# Power_Sources.net
KiCad netlist of a schematic drawn in Altium Designer
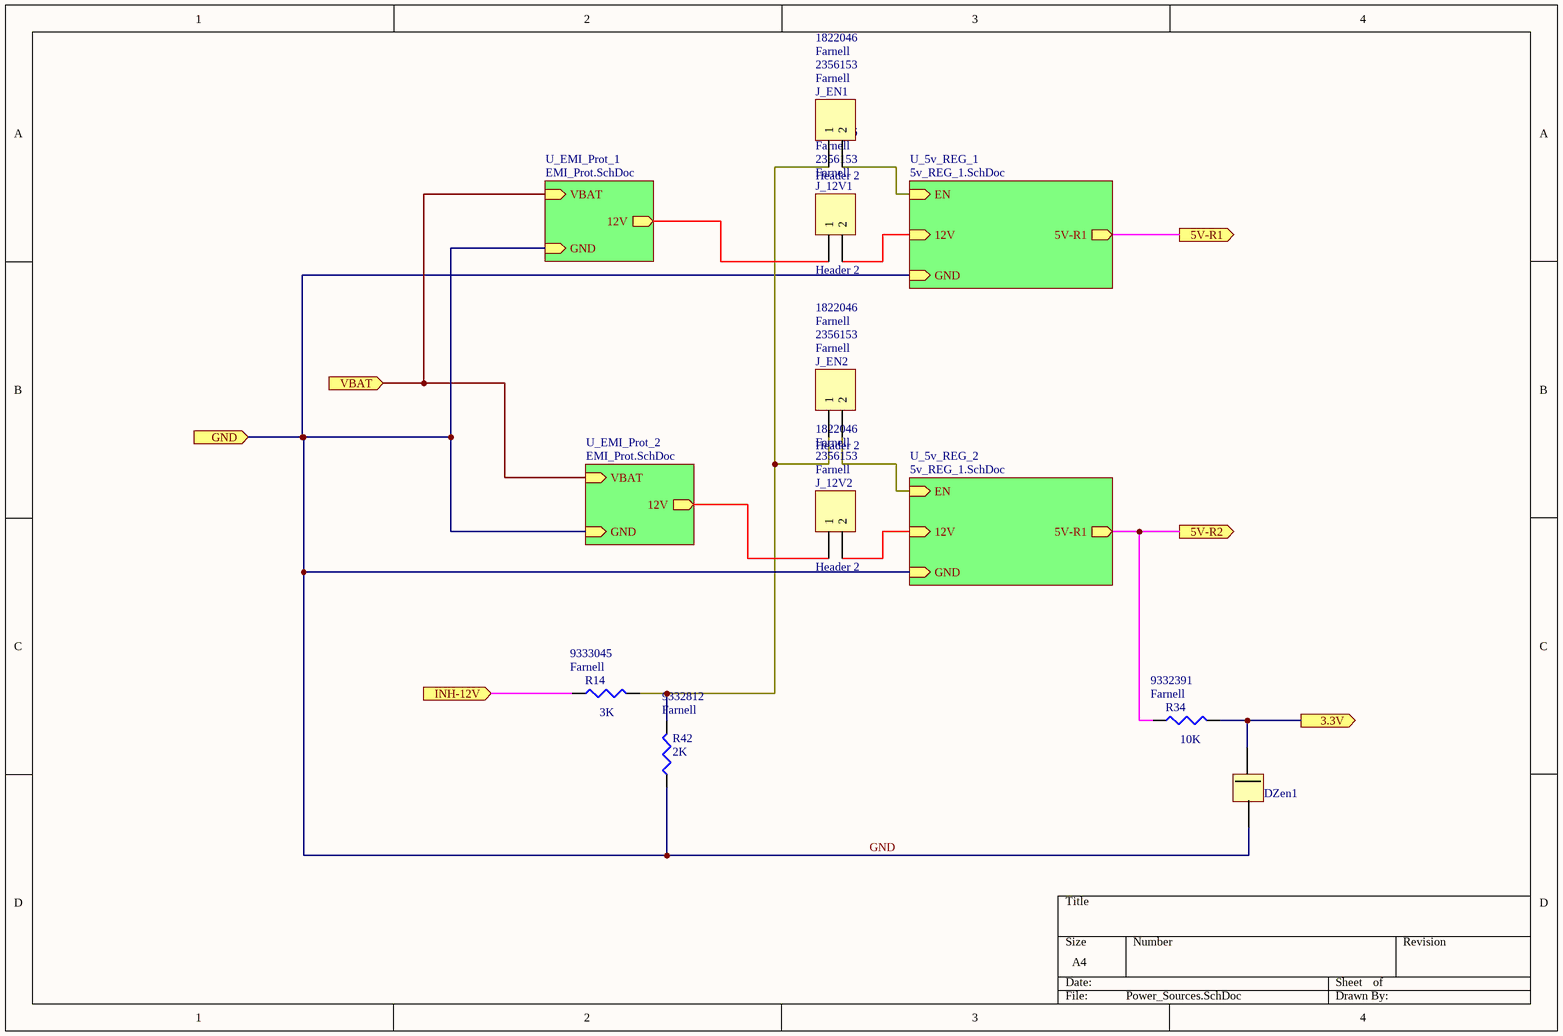
[diagram p0: Power_Sources.SchDoc]

(export (version "E")
  (design (tool "Eeschema 10.0.6"))
  (components
    (comp (ref "DZen1")
      (value "3.3V")
      (footprint "Zener_Diode")
      (description "Zener Diode 3.3V")
      (libsource (lib "Schlib1_HMI3D") (part "D_Zener"))
    )
    (comp (ref "J_12V1")
      (value "Header 2")
      (footprint "HDR1X2")
      (description "Header, 2-Pin")
      (fields
        (field (name "SUPPLIER 1") "Farnell")
        (field (name "SUPPLIER PART NUMBER 1") "2356153")
        (field (name "SUPPLIER 2") "Farnell")
        (field (name "SUPPLIER PART NUMBER 2") "1822046")
        (field (name "PUBLISHER") "Altium Limited")
      )
      (libsource (lib "Miscellaneous Connectors") (part "Header 2"))
    )
    (comp (ref "J_12V2")
      (value "Header 2")
      (footprint "HDR1X2")
      (description "Header, 2-Pin")
      (fields
        (field (name "SUPPLIER 1") "Farnell")
        (field (name "SUPPLIER PART NUMBER 1") "2356153")
        (field (name "SUPPLIER 2") "Farnell")
        (field (name "SUPPLIER PART NUMBER 2") "1822046")
        (field (name "PUBLISHER") "Altium Limited")
      )
      (libsource (lib "Miscellaneous Connectors") (part "Header 2"))
    )
    (comp (ref "J_EN1")
      (value "Header 2")
      (footprint "HDR1X2")
      (description "Header, 2-Pin")
      (fields
        (field (name "SUPPLIER 1") "Farnell")
        (field (name "SUPPLIER PART NUMBER 1") "2356153")
        (field (name "SUPPLIER 2") "Farnell")
        (field (name "SUPPLIER PART NUMBER 2") "1822046")
        (field (name "PUBLISHER") "Altium Limited")
      )
      (libsource (lib "Miscellaneous Connectors") (part "Header 2"))
    )
    (comp (ref "J_EN2")
      (value "Header 2")
      (footprint "HDR1X2")
      (description "Header, 2-Pin")
      (fields
        (field (name "SUPPLIER 1") "Farnell")
        (field (name "SUPPLIER PART NUMBER 1") "2356153")
        (field (name "SUPPLIER 2") "Farnell")
        (field (name "SUPPLIER PART NUMBER 2") "1822046")
        (field (name "PUBLISHER") "Altium Limited")
      )
      (libsource (lib "Miscellaneous Connectors") (part "Header 2"))
    )
    (comp (ref "R14")
      (value "3K")
      (footprint "RES_0805")
      (description "Resistor")
      (fields
        (field (name "SUPPLIER 1") "Farnell")
        (field (name "SUPPLIER PART NUMBER 1") "9333045")
        (field (name "PUBLISHER") "Altium Limited")
      )
      (libsource (lib "Miscellaneous Devices") (part "Res3"))
    )
    (comp (ref "R34")
      (value "10K")
      (footprint "RES_0805")
      (description "Resistor")
      (fields
        (field (name "SUPPLIER 1") "Farnell")
        (field (name "SUPPLIER PART NUMBER 1") "9332391")
        (field (name "PUBLISHER") "Altium Limited")
      )
      (libsource (lib "Miscellaneous Devices") (part "Res3"))
    )
    (comp (ref "R42")
      (value "2K")
      (footprint "RES_0805")
      (description "Resistor")
      (fields
        (field (name "SUPPLIER 1") "Farnell")
        (field (name "SUPPLIER PART NUMBER 1") "9332812")
        (field (name "PUBLISHER") "Altium Limited")
      )
      (libsource (lib "Miscellaneous Devices") (part "Res3"))
    )
  )
  (nets
    (net (code "1") (name "/3.3V") (class "Default")
      (node (ref "DZen1") (pin "D1") (pinfunction "D1_D1") (pintype "passive"))
      (node (ref "R34") (pin "2") (pinfunction "2_2") (pintype "passive"))
    )
    (net (code "3") (name "/5V-R2") (class "Default")
      (node (ref "R34") (pin "1") (pinfunction "1_1") (pintype "passive"))
    )
    (net (code "4") (name "/12V") (class "Default")
      (node (ref "J_12V1") (pin "2") (pinfunction "2_2") (pintype "passive"))
    )
    (net (code "5") (name "/12V_1") (class "Default")
      (node (ref "J_12V2") (pin "2") (pinfunction "2_2") (pintype "passive"))
    )
    (net (code "6") (name "/12V_2") (class "Default")
      (node (ref "J_12V2") (pin "1") (pinfunction "1_1") (pintype "passive"))
    )
    (net (code "7") (name "/12V_3") (class "Default")
      (node (ref "J_12V1") (pin "1") (pinfunction "1_1") (pintype "passive"))
    )
    (net (code "8") (name "/EN") (class "Default")
      (node (ref "J_EN1") (pin "2") (pinfunction "2_2") (pintype "passive"))
    )
    (net (code "9") (name "/EN_1") (class "Default")
      (node (ref "J_EN2") (pin "2") (pinfunction "2_2") (pintype "passive"))
    )
    (net (code "10") (name "/GND") (class "Default")
      (node (ref "DZen1") (pin "D2") (pinfunction "D2_D2") (pintype "passive"))
      (node (ref "R42") (pin "1") (pinfunction "1_1") (pintype "passive"))
    )
    (net (code "11") (name "/INH-12V") (class "Default")
      (node (ref "R14") (pin "1") (pinfunction "1_1") (pintype "passive"))
    )
    (net (code "13") (name "Net-(J_EN1-Pad1)") (class "Default")
      (node (ref "J_EN1") (pin "1") (pinfunction "1_1") (pintype "passive"))
      (node (ref "J_EN2") (pin "1") (pinfunction "1_1") (pintype "passive"))
      (node (ref "R14") (pin "2") (pinfunction "2_2") (pintype "passive"))
      (node (ref "R42") (pin "2") (pinfunction "2_2") (pintype "passive"))
    )
  )
)
